# RF_Transceiver_Module.net
KiCad netlist of a schematic drawn in Altium Designer
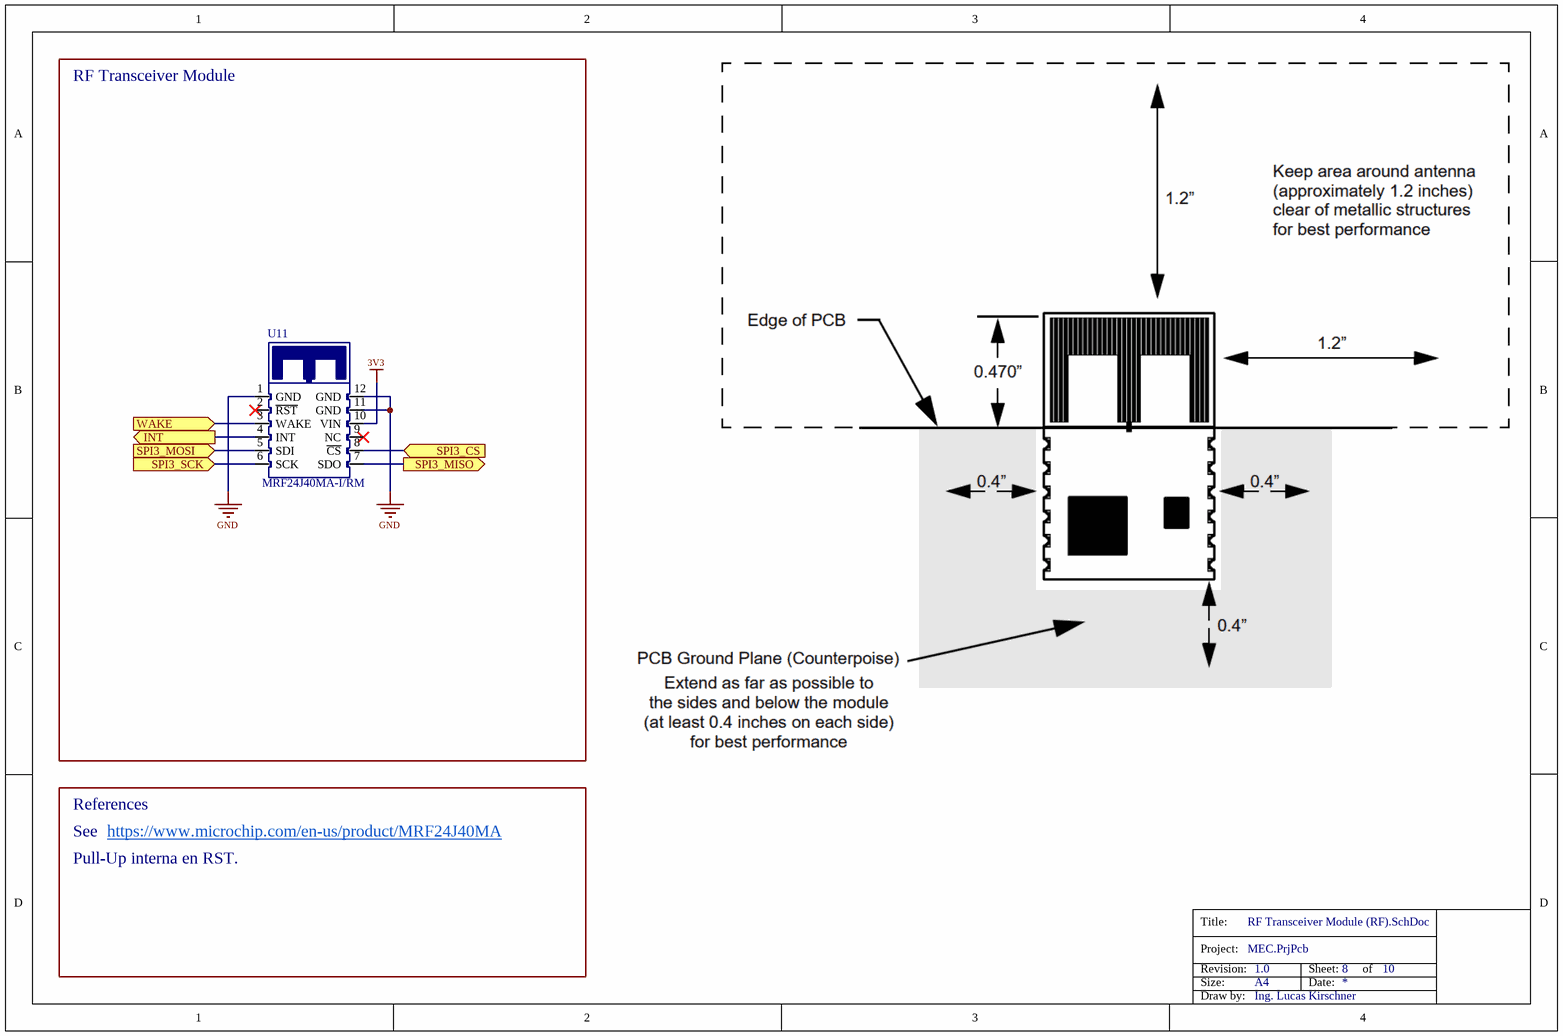
[diagram p0: RF Transceiver Module (RF).SchDoc]

(export (version "E")
  (design (tool "Eeschema 10.0.6"))
  (components
    (comp (ref "U11")
      (value "RF Transceiver Module")
      (footprint "PKG1100X700-12N")
      (description "Zigbee Modules - 802.15.4 2.4GHz IEEE 802.15.4 Transceiver Module")
      (fields
        (field (name "MANUFACTURER") "Microchip")
        (field (name "MOUSER PART #") "579-MRF24J40MA-I/RM")
        (field (name "PART NUMBER") "MRF24J40MA-I/RM")
      )
      (libsource (lib "SchLib") (part "U-MRF24J40MA"))
    )
  )
  (nets
    (net (code "1") (name "/INT") (class "Default")
      (node (ref "U11") (pin "4") (pinfunction "INT_4") (pintype "passive"))
    )
    (net (code "2") (name "/SPI3_CS") (class "Default")
      (node (ref "U11") (pin "8") (pinfunction "~{CS}_8") (pintype "passive"))
    )
    (net (code "3") (name "/SPI3_MISO") (class "Default")
      (node (ref "U11") (pin "7") (pinfunction "SDO_7") (pintype "passive"))
    )
    (net (code "4") (name "/SPI3_MOSI") (class "Default")
      (node (ref "U11") (pin "5") (pinfunction "SDI_5") (pintype "passive"))
    )
    (net (code "5") (name "/SPI3_SCK") (class "Default")
      (node (ref "U11") (pin "6") (pinfunction "SCK_6") (pintype "passive"))
    )
    (net (code "6") (name "/WAKE") (class "Default")
      (node (ref "U11") (pin "3") (pinfunction "WAKE_3") (pintype "passive"))
    )
    (net (code "7") (name "3V3") (class "Default")
      (node (ref "U11") (pin "10") (pinfunction "VIN_10") (pintype "passive"))
    )
    (net (code "8") (name "GND") (class "Default")
      (node (ref "U11") (pin "1") (pinfunction "GND_1") (pintype "passive"))
      (node (ref "U11") (pin "11") (pinfunction "GND_11") (pintype "passive"))
      (node (ref "U11") (pin "12") (pinfunction "GND_12") (pintype "passive"))
    )
    (net (code "9") (name "unconnected-(U11-NC-Pad9)") (class "Default")
      (node (ref "U11") (pin "9") (pinfunction "NC_9") (pintype "passive+no_connect"))
    )
    (net (code "10") (name "unconnected-(U11-~{RST}-Pad2)") (class "Default")
      (node (ref "U11") (pin "2") (pinfunction "~{RST}_2") (pintype "passive+no_connect"))
    )
  )
)
